# Issaimaru.net
KiCad netlist of a schematic drawn in EAGLE
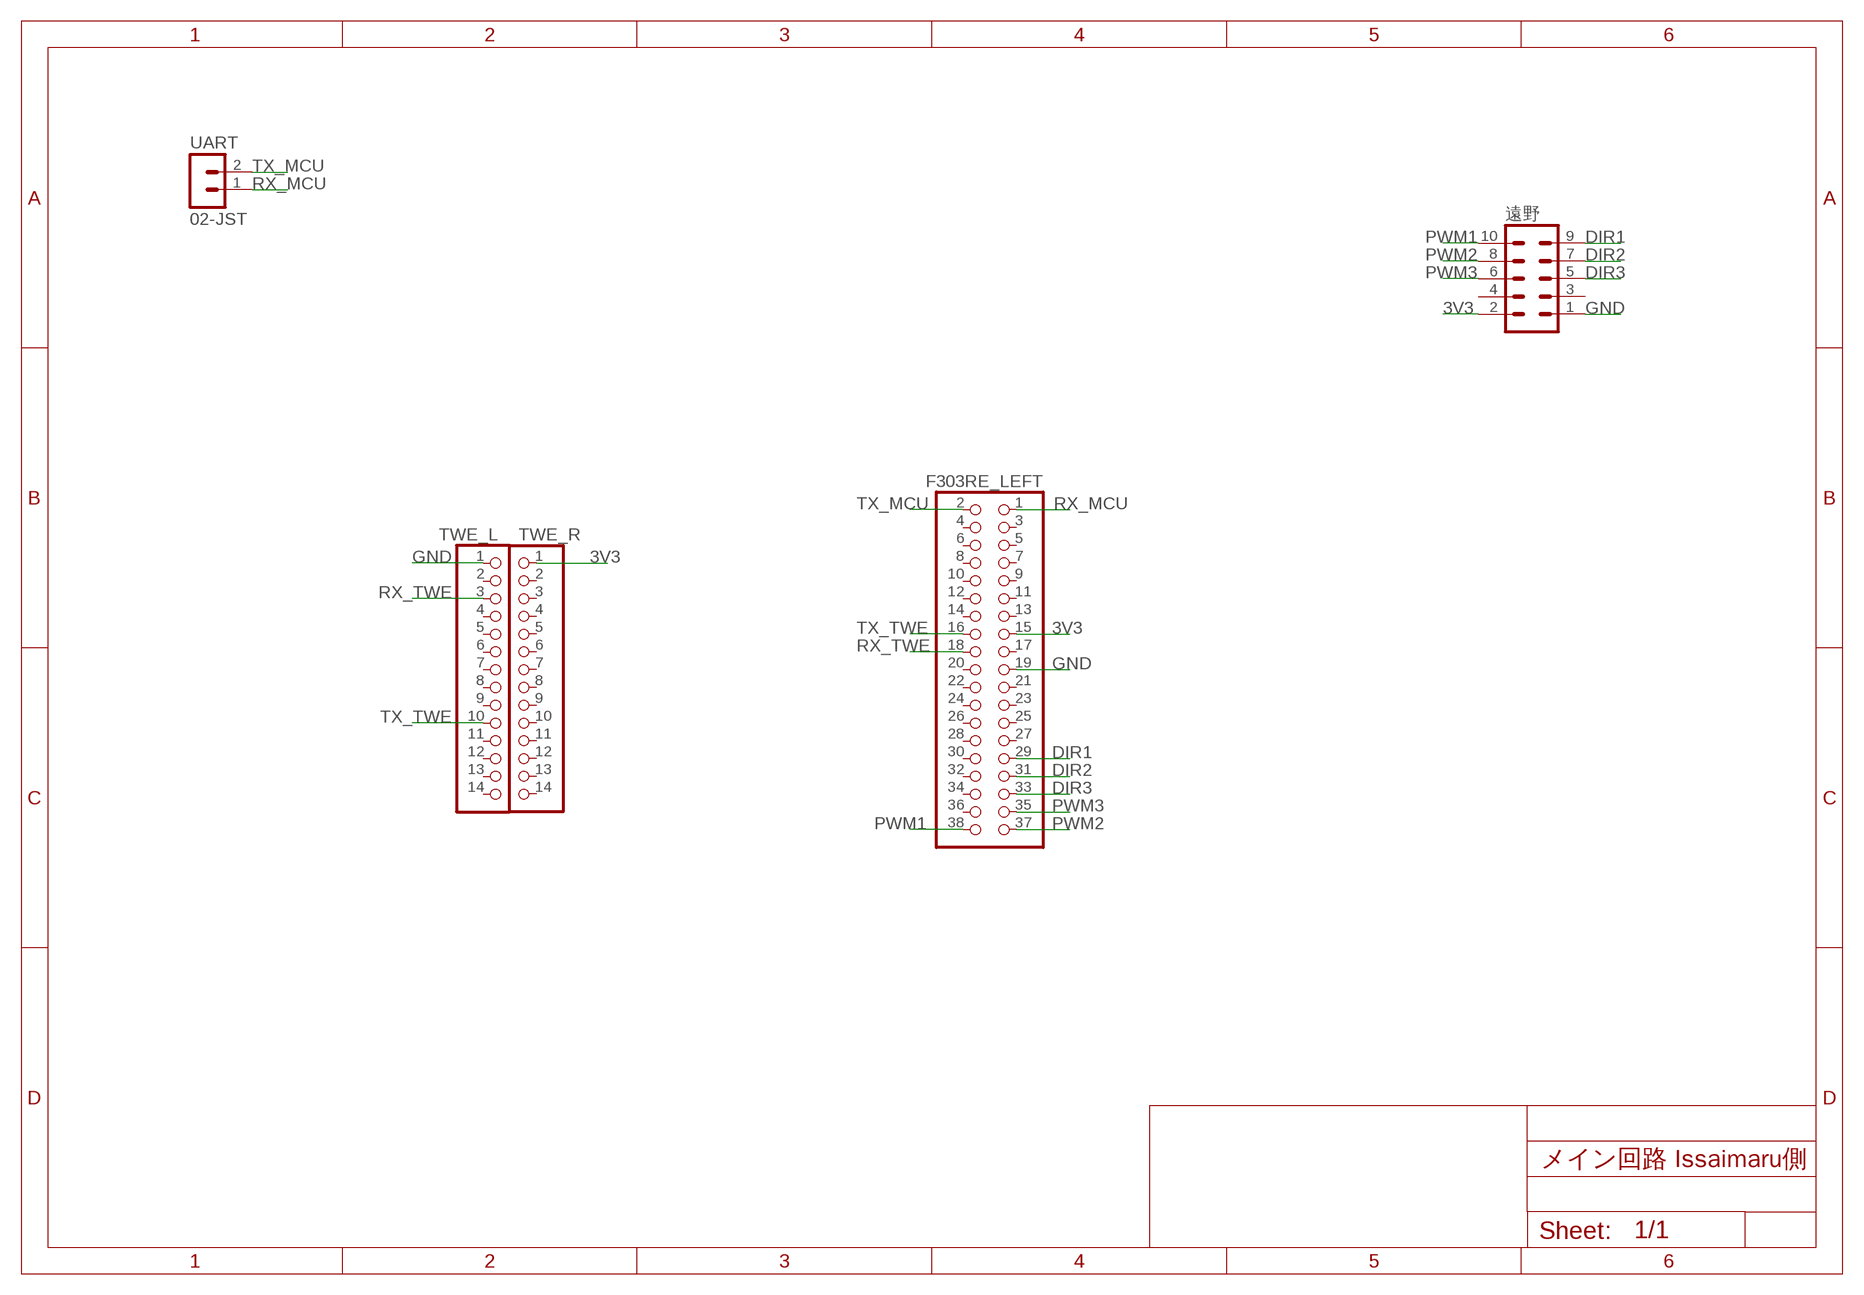
[diagram p0: schematic, sheet 1]

(export (version "E")
  (design (tool "Eeschema 10.0.6"))
  (components
    (comp (ref "F303RE_LEFT")
      (value "PINHD-2X19")
      (footprint "eagle-import:2X19")
      (libsource (lib "eagle-import") (part "PINHD-2X19"))
    )
    (comp (ref "TWE_L")
      (value "PINHD-1X14")
      (footprint "eagle-import:1X14")
      (libsource (lib "eagle-import") (part "PINHD-1X14"))
    )
    (comp (ref "TWE_R")
      (value "PINHD-1X14")
      (footprint "eagle-import:1X14")
      (libsource (lib "eagle-import") (part "PINHD-1X14"))
    )
    (comp (ref "UART")
      (value "02-JST")
      (footprint "eagle-import:B2B-XH")
      (libsource (lib "eagle-import") (part "02-JST"))
    )
    (comp (ref "遠野")
      (value "ML10")
      (footprint "eagle-import:ML10")
      (libsource (lib "eagle-import") (part "ML10"))
    )
  )
  (nets
    (net (code "1") (name "/3V3") (class "Default")
      (node (ref "F303RE_LEFT") (pin "15") (pinfunction "15_15") (pintype "passive"))
      (node (ref "TWE_R") (pin "1") (pinfunction "1_1") (pintype "passive"))
      (node (ref "遠野") (pin "2") (pinfunction "2_2") (pintype "passive"))
    )
    (net (code "2") (name "/DIR1") (class "Default")
      (node (ref "F303RE_LEFT") (pin "29") (pinfunction "29_29") (pintype "passive"))
      (node (ref "遠野") (pin "9") (pinfunction "9_9") (pintype "passive"))
    )
    (net (code "3") (name "/DIR2") (class "Default")
      (node (ref "F303RE_LEFT") (pin "31") (pinfunction "31_31") (pintype "passive"))
      (node (ref "遠野") (pin "7") (pinfunction "7_7") (pintype "passive"))
    )
    (net (code "4") (name "/DIR3") (class "Default")
      (node (ref "F303RE_LEFT") (pin "33") (pinfunction "33_33") (pintype "passive"))
      (node (ref "遠野") (pin "5") (pinfunction "5_5") (pintype "passive"))
    )
    (net (code "5") (name "/GND") (class "Default")
      (node (ref "F303RE_LEFT") (pin "19") (pinfunction "19_19") (pintype "passive"))
      (node (ref "TWE_L") (pin "1") (pinfunction "1_1") (pintype "passive"))
      (node (ref "遠野") (pin "1") (pinfunction "1_1") (pintype "passive"))
    )
    (net (code "6") (name "/PWM1") (class "Default")
      (node (ref "F303RE_LEFT") (pin "38") (pinfunction "38_38") (pintype "passive"))
      (node (ref "遠野") (pin "10") (pinfunction "10_10") (pintype "passive"))
    )
    (net (code "7") (name "/PWM2") (class "Default")
      (node (ref "F303RE_LEFT") (pin "37") (pinfunction "37_37") (pintype "passive"))
      (node (ref "遠野") (pin "8") (pinfunction "8_8") (pintype "passive"))
    )
    (net (code "8") (name "/PWM3") (class "Default")
      (node (ref "F303RE_LEFT") (pin "35") (pinfunction "35_35") (pintype "passive"))
      (node (ref "遠野") (pin "6") (pinfunction "6_6") (pintype "passive"))
    )
    (net (code "9") (name "/RX_MCU") (class "Default")
      (node (ref "F303RE_LEFT") (pin "1") (pinfunction "1_1") (pintype "passive"))
      (node (ref "UART") (pin "1") (pinfunction "1_1") (pintype "passive"))
    )
    (net (code "10") (name "/RX_TWE") (class "Default")
      (node (ref "F303RE_LEFT") (pin "18") (pinfunction "18_18") (pintype "passive"))
      (node (ref "TWE_L") (pin "3") (pinfunction "3_3") (pintype "passive"))
    )
    (net (code "11") (name "/TX_MCU") (class "Default")
      (node (ref "F303RE_LEFT") (pin "2") (pinfunction "2_2") (pintype "passive"))
      (node (ref "UART") (pin "2") (pinfunction "2_2") (pintype "passive"))
    )
    (net (code "12") (name "/TX_TWE") (class "Default")
      (node (ref "F303RE_LEFT") (pin "16") (pinfunction "16_16") (pintype "passive"))
      (node (ref "TWE_L") (pin "10") (pinfunction "10_10") (pintype "passive"))
    )
    (net (code "13") (name "unconnected-(F303RE_LEFT-Pad3)") (class "Default")
      (node (ref "F303RE_LEFT") (pin "3") (pinfunction "3_3") (pintype "passive"))
    )
    (net (code "14") (name "unconnected-(F303RE_LEFT-Pad4)") (class "Default")
      (node (ref "F303RE_LEFT") (pin "4") (pinfunction "4_4") (pintype "passive"))
    )
    (net (code "15") (name "unconnected-(F303RE_LEFT-Pad5)") (class "Default")
      (node (ref "F303RE_LEFT") (pin "5") (pinfunction "5_5") (pintype "passive"))
    )
    (net (code "16") (name "unconnected-(F303RE_LEFT-Pad6)") (class "Default")
      (node (ref "F303RE_LEFT") (pin "6") (pinfunction "6_6") (pintype "passive"))
    )
    (net (code "17") (name "unconnected-(F303RE_LEFT-Pad7)") (class "Default")
      (node (ref "F303RE_LEFT") (pin "7") (pinfunction "7_7") (pintype "passive"))
    )
    (net (code "18") (name "unconnected-(F303RE_LEFT-Pad8)") (class "Default")
      (node (ref "F303RE_LEFT") (pin "8") (pinfunction "8_8") (pintype "passive"))
    )
    (net (code "19") (name "unconnected-(F303RE_LEFT-Pad9)") (class "Default")
      (node (ref "F303RE_LEFT") (pin "9") (pinfunction "9_9") (pintype "passive"))
    )
    (net (code "20") (name "unconnected-(F303RE_LEFT-Pad10)") (class "Default")
      (node (ref "F303RE_LEFT") (pin "10") (pinfunction "10_10") (pintype "passive"))
    )
    (net (code "21") (name "unconnected-(F303RE_LEFT-Pad11)") (class "Default")
      (node (ref "F303RE_LEFT") (pin "11") (pinfunction "11_11") (pintype "passive"))
    )
    (net (code "22") (name "unconnected-(F303RE_LEFT-Pad12)") (class "Default")
      (node (ref "F303RE_LEFT") (pin "12") (pinfunction "12_12") (pintype "passive"))
    )
    (net (code "23") (name "unconnected-(F303RE_LEFT-Pad13)") (class "Default")
      (node (ref "F303RE_LEFT") (pin "13") (pinfunction "13_13") (pintype "passive"))
    )
    (net (code "24") (name "unconnected-(F303RE_LEFT-Pad14)") (class "Default")
      (node (ref "F303RE_LEFT") (pin "14") (pinfunction "14_14") (pintype "passive"))
    )
    (net (code "25") (name "unconnected-(F303RE_LEFT-Pad17)") (class "Default")
      (node (ref "F303RE_LEFT") (pin "17") (pinfunction "17_17") (pintype "passive"))
    )
    (net (code "26") (name "unconnected-(F303RE_LEFT-Pad20)") (class "Default")
      (node (ref "F303RE_LEFT") (pin "20") (pinfunction "20_20") (pintype "passive"))
    )
    (net (code "27") (name "unconnected-(F303RE_LEFT-Pad21)") (class "Default")
      (node (ref "F303RE_LEFT") (pin "21") (pinfunction "21_21") (pintype "passive"))
    )
    (net (code "28") (name "unconnected-(F303RE_LEFT-Pad22)") (class "Default")
      (node (ref "F303RE_LEFT") (pin "22") (pinfunction "22_22") (pintype "passive"))
    )
    (net (code "29") (name "unconnected-(F303RE_LEFT-Pad23)") (class "Default")
      (node (ref "F303RE_LEFT") (pin "23") (pinfunction "23_23") (pintype "passive"))
    )
    (net (code "30") (name "unconnected-(F303RE_LEFT-Pad24)") (class "Default")
      (node (ref "F303RE_LEFT") (pin "24") (pinfunction "24_24") (pintype "passive"))
    )
    (net (code "31") (name "unconnected-(F303RE_LEFT-Pad25)") (class "Default")
      (node (ref "F303RE_LEFT") (pin "25") (pinfunction "25_25") (pintype "passive"))
    )
    (net (code "32") (name "unconnected-(F303RE_LEFT-Pad26)") (class "Default")
      (node (ref "F303RE_LEFT") (pin "26") (pinfunction "26_26") (pintype "passive"))
    )
    (net (code "33") (name "unconnected-(F303RE_LEFT-Pad27)") (class "Default")
      (node (ref "F303RE_LEFT") (pin "27") (pinfunction "27_27") (pintype "passive"))
    )
    (net (code "34") (name "unconnected-(F303RE_LEFT-Pad28)") (class "Default")
      (node (ref "F303RE_LEFT") (pin "28") (pinfunction "28_28") (pintype "passive"))
    )
    (net (code "35") (name "unconnected-(F303RE_LEFT-Pad30)") (class "Default")
      (node (ref "F303RE_LEFT") (pin "30") (pinfunction "30_30") (pintype "passive"))
    )
    (net (code "36") (name "unconnected-(F303RE_LEFT-Pad32)") (class "Default")
      (node (ref "F303RE_LEFT") (pin "32") (pinfunction "32_32") (pintype "passive"))
    )
    (net (code "37") (name "unconnected-(F303RE_LEFT-Pad34)") (class "Default")
      (node (ref "F303RE_LEFT") (pin "34") (pinfunction "34_34") (pintype "passive"))
    )
    (net (code "38") (name "unconnected-(F303RE_LEFT-Pad36)") (class "Default")
      (node (ref "F303RE_LEFT") (pin "36") (pinfunction "36_36") (pintype "passive"))
    )
    (net (code "39") (name "unconnected-(TWE_L-Pad2)") (class "Default")
      (node (ref "TWE_L") (pin "2") (pinfunction "2_2") (pintype "passive"))
    )
    (net (code "40") (name "unconnected-(TWE_L-Pad4)") (class "Default")
      (node (ref "TWE_L") (pin "4") (pinfunction "4_4") (pintype "passive"))
    )
    (net (code "41") (name "unconnected-(TWE_L-Pad5)") (class "Default")
      (node (ref "TWE_L") (pin "5") (pinfunction "5_5") (pintype "passive"))
    )
    (net (code "42") (name "unconnected-(TWE_L-Pad6)") (class "Default")
      (node (ref "TWE_L") (pin "6") (pinfunction "6_6") (pintype "passive"))
    )
    (net (code "43") (name "unconnected-(TWE_L-Pad7)") (class "Default")
      (node (ref "TWE_L") (pin "7") (pinfunction "7_7") (pintype "passive"))
    )
    (net (code "44") (name "unconnected-(TWE_L-Pad8)") (class "Default")
      (node (ref "TWE_L") (pin "8") (pinfunction "8_8") (pintype "passive"))
    )
    (net (code "45") (name "unconnected-(TWE_L-Pad9)") (class "Default")
      (node (ref "TWE_L") (pin "9") (pinfunction "9_9") (pintype "passive"))
    )
    (net (code "46") (name "unconnected-(TWE_L-Pad11)") (class "Default")
      (node (ref "TWE_L") (pin "11") (pinfunction "11_11") (pintype "passive"))
    )
    (net (code "47") (name "unconnected-(TWE_L-Pad12)") (class "Default")
      (node (ref "TWE_L") (pin "12") (pinfunction "12_12") (pintype "passive"))
    )
    (net (code "48") (name "unconnected-(TWE_L-Pad13)") (class "Default")
      (node (ref "TWE_L") (pin "13") (pinfunction "13_13") (pintype "passive"))
    )
    (net (code "49") (name "unconnected-(TWE_L-Pad14)") (class "Default")
      (node (ref "TWE_L") (pin "14") (pinfunction "14_14") (pintype "passive"))
    )
    (net (code "50") (name "unconnected-(TWE_R-Pad2)") (class "Default")
      (node (ref "TWE_R") (pin "2") (pinfunction "2_2") (pintype "passive"))
    )
    (net (code "51") (name "unconnected-(TWE_R-Pad3)") (class "Default")
      (node (ref "TWE_R") (pin "3") (pinfunction "3_3") (pintype "passive"))
    )
    (net (code "52") (name "unconnected-(TWE_R-Pad4)") (class "Default")
      (node (ref "TWE_R") (pin "4") (pinfunction "4_4") (pintype "passive"))
    )
    (net (code "53") (name "unconnected-(TWE_R-Pad5)") (class "Default")
      (node (ref "TWE_R") (pin "5") (pinfunction "5_5") (pintype "passive"))
    )
    (net (code "54") (name "unconnected-(TWE_R-Pad6)") (class "Default")
      (node (ref "TWE_R") (pin "6") (pinfunction "6_6") (pintype "passive"))
    )
    (net (code "55") (name "unconnected-(TWE_R-Pad7)") (class "Default")
      (node (ref "TWE_R") (pin "7") (pinfunction "7_7") (pintype "passive"))
    )
    (net (code "56") (name "unconnected-(TWE_R-Pad8)") (class "Default")
      (node (ref "TWE_R") (pin "8") (pinfunction "8_8") (pintype "passive"))
    )
    (net (code "57") (name "unconnected-(TWE_R-Pad9)") (class "Default")
      (node (ref "TWE_R") (pin "9") (pinfunction "9_9") (pintype "passive"))
    )
    (net (code "58") (name "unconnected-(TWE_R-Pad10)") (class "Default")
      (node (ref "TWE_R") (pin "10") (pinfunction "10_10") (pintype "passive"))
    )
    (net (code "59") (name "unconnected-(TWE_R-Pad11)") (class "Default")
      (node (ref "TWE_R") (pin "11") (pinfunction "11_11") (pintype "passive"))
    )
    (net (code "60") (name "unconnected-(TWE_R-Pad12)") (class "Default")
      (node (ref "TWE_R") (pin "12") (pinfunction "12_12") (pintype "passive"))
    )
    (net (code "61") (name "unconnected-(TWE_R-Pad13)") (class "Default")
      (node (ref "TWE_R") (pin "13") (pinfunction "13_13") (pintype "passive"))
    )
    (net (code "62") (name "unconnected-(TWE_R-Pad14)") (class "Default")
      (node (ref "TWE_R") (pin "14") (pinfunction "14_14") (pintype "passive"))
    )
    (net (code "63") (name "unconnected-(遠野-Pad3)") (class "Default")
      (node (ref "遠野") (pin "3") (pinfunction "3_3") (pintype "passive"))
    )
    (net (code "64") (name "unconnected-(遠野-Pad4)") (class "Default")
      (node (ref "遠野") (pin "4") (pinfunction "4_4") (pintype "passive"))
    )
  )
)
